# G851B.net
KiCad netlist of a schematic drawn in EAGLE
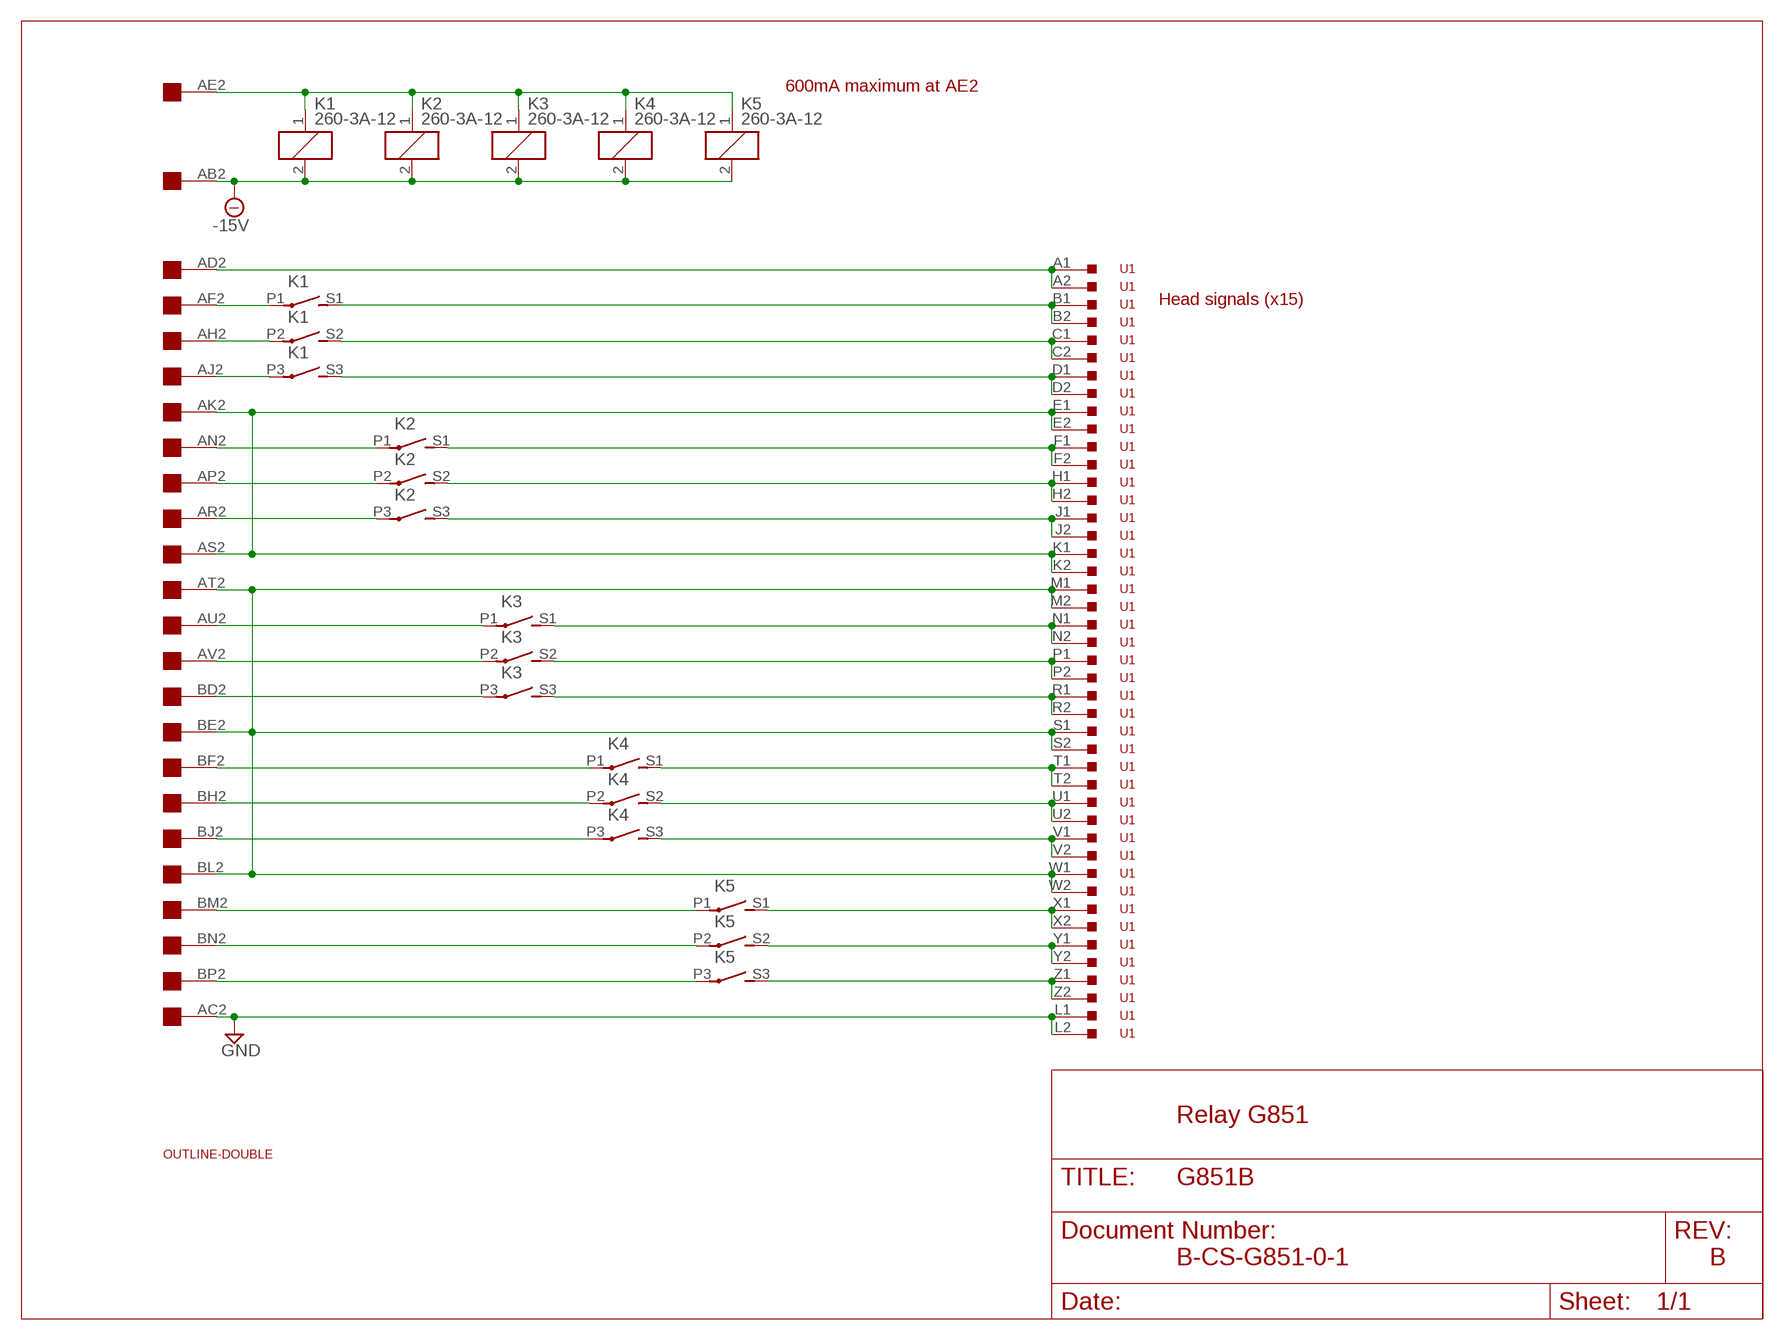
[diagram p0: schematic, sheet 1]

(export (version "E")
  (design (tool "Eeschema 10.0.6"))
  (components
    (comp (ref "K1")
      (value "260-3A-12")
      (footprint "eagle-import:260-3A-12")
      (libsource (lib "eagle-import") (part "260-3A-12"))
    )
    (comp (ref "K2")
      (value "260-3A-12")
      (footprint "eagle-import:260-3A-12")
      (libsource (lib "eagle-import") (part "260-3A-12"))
    )
    (comp (ref "K3")
      (value "260-3A-12")
      (footprint "eagle-import:260-3A-12")
      (libsource (lib "eagle-import") (part "260-3A-12"))
    )
    (comp (ref "K4")
      (value "260-3A-12")
      (footprint "eagle-import:260-3A-12")
      (libsource (lib "eagle-import") (part "260-3A-12"))
    )
    (comp (ref "K5")
      (value "260-3A-12")
      (footprint "eagle-import:260-3A-12")
      (libsource (lib "eagle-import") (part "260-3A-12"))
    )
    (comp (ref "U$1")
      (value "DOUBLE")
      (footprint "eagle-import:EDGE-CON4")
      (libsource (lib "eagle-import") (part "DOUBLE"))
    )
    (comp (ref "U$3")
      (value "OUTLINE-DOUBLE")
      (footprint "eagle-import:DOUBLE")
      (libsource (lib "eagle-import") (part "OUTLINE-DOUBLE"))
    )
    (comp (ref "U1")
      (value "133-022-03")
      (footprint "eagle-import:133-022-03")
      (libsource (lib "eagle-import") (part "133-022-03"))
    )
  )
  (nets
    (net (code "1") (name "-15V") (class "Default")
      (node (ref "K1") (pin "2") (pinfunction "2_2") (pintype "passive"))
      (node (ref "K2") (pin "2") (pinfunction "2_2") (pintype "passive"))
      (node (ref "K3") (pin "2") (pinfunction "2_2") (pintype "passive"))
      (node (ref "K4") (pin "2") (pinfunction "2_2") (pintype "passive"))
      (node (ref "K5") (pin "2") (pinfunction "2_2") (pintype "passive"))
      (node (ref "U$1") (pin "AB2") (pinfunction "1_AB2") (pintype "bidirectional"))
    )
    (net (code "2") (name "GND") (class "Default")
      (node (ref "U$1") (pin "AC2") (pinfunction "1_AC2") (pintype "bidirectional"))
      (node (ref "U1") (pin "L1") (pinfunction "P$2_L1") (pintype "bidirectional"))
      (node (ref "U1") (pin "L2") (pinfunction "P$2_L2") (pintype "bidirectional"))
    )
    (net (code "3") (name "Net-(K1B-P)") (class "Default")
      (node (ref "K1") (pin "P1") (pinfunction "P_P1") (pintype "passive"))
      (node (ref "U$1") (pin "AF2") (pinfunction "1_AF2") (pintype "bidirectional"))
    )
    (net (code "4") (name "Net-(K1B-S)") (class "Default")
      (node (ref "K1") (pin "S1") (pinfunction "S_S1") (pintype "passive"))
      (node (ref "U1") (pin "B1") (pinfunction "P$2_B1") (pintype "bidirectional"))
      (node (ref "U1") (pin "B2") (pinfunction "P$2_B2") (pintype "bidirectional"))
    )
    (net (code "5") (name "Net-(K1C-P)") (class "Default")
      (node (ref "K1") (pin "P2") (pinfunction "P_P2") (pintype "passive"))
      (node (ref "U$1") (pin "AH2") (pinfunction "1_AH2") (pintype "bidirectional"))
    )
    (net (code "6") (name "Net-(K1C-S)") (class "Default")
      (node (ref "K1") (pin "S2") (pinfunction "S_S2") (pintype "passive"))
      (node (ref "U1") (pin "C1") (pinfunction "P$2_C1") (pintype "bidirectional"))
      (node (ref "U1") (pin "C2") (pinfunction "P$2_C2") (pintype "bidirectional"))
    )
    (net (code "7") (name "Net-(K1D-P)") (class "Default")
      (node (ref "K1") (pin "P3") (pinfunction "P_P3") (pintype "passive"))
      (node (ref "U$1") (pin "AJ2") (pinfunction "1_AJ2") (pintype "bidirectional"))
    )
    (net (code "8") (name "Net-(K1D-S)") (class "Default")
      (node (ref "K1") (pin "S3") (pinfunction "S_S3") (pintype "passive"))
      (node (ref "U1") (pin "D1") (pinfunction "P$2_D1") (pintype "bidirectional"))
      (node (ref "U1") (pin "D2") (pinfunction "P$2_D2") (pintype "bidirectional"))
    )
    (net (code "9") (name "Net-(K2B-P)") (class "Default")
      (node (ref "K2") (pin "P1") (pinfunction "P_P1") (pintype "passive"))
      (node (ref "U$1") (pin "AN2") (pinfunction "1_AN2") (pintype "bidirectional"))
    )
    (net (code "10") (name "Net-(K2B-S)") (class "Default")
      (node (ref "K2") (pin "S1") (pinfunction "S_S1") (pintype "passive"))
      (node (ref "U1") (pin "F1") (pinfunction "P$2_F1") (pintype "bidirectional"))
      (node (ref "U1") (pin "F2") (pinfunction "P$2_F2") (pintype "bidirectional"))
    )
    (net (code "11") (name "Net-(K2C-P)") (class "Default")
      (node (ref "K2") (pin "P2") (pinfunction "P_P2") (pintype "passive"))
      (node (ref "U$1") (pin "AP2") (pinfunction "1_AP2") (pintype "bidirectional"))
    )
    (net (code "12") (name "Net-(K2C-S)") (class "Default")
      (node (ref "K2") (pin "S2") (pinfunction "S_S2") (pintype "passive"))
      (node (ref "U1") (pin "H1") (pinfunction "P$2_H1") (pintype "bidirectional"))
      (node (ref "U1") (pin "H2") (pinfunction "P$2_H2") (pintype "bidirectional"))
    )
    (net (code "13") (name "Net-(K2D-P)") (class "Default")
      (node (ref "K2") (pin "P3") (pinfunction "P_P3") (pintype "passive"))
      (node (ref "U$1") (pin "AR2") (pinfunction "1_AR2") (pintype "bidirectional"))
    )
    (net (code "14") (name "Net-(K2D-S)") (class "Default")
      (node (ref "K2") (pin "S3") (pinfunction "S_S3") (pintype "passive"))
      (node (ref "U1") (pin "J1") (pinfunction "P$2_J1") (pintype "bidirectional"))
      (node (ref "U1") (pin "J2") (pinfunction "P$2_J2") (pintype "bidirectional"))
    )
    (net (code "15") (name "Net-(K3B-P)") (class "Default")
      (node (ref "K3") (pin "P1") (pinfunction "P_P1") (pintype "passive"))
      (node (ref "U$1") (pin "AU2") (pinfunction "1_AU2") (pintype "bidirectional"))
    )
    (net (code "16") (name "Net-(K3B-S)") (class "Default")
      (node (ref "K3") (pin "S1") (pinfunction "S_S1") (pintype "passive"))
      (node (ref "U1") (pin "N1") (pinfunction "P$2_N1") (pintype "bidirectional"))
      (node (ref "U1") (pin "N2") (pinfunction "P$2_N2") (pintype "bidirectional"))
    )
    (net (code "17") (name "Net-(K3C-P)") (class "Default")
      (node (ref "K3") (pin "P2") (pinfunction "P_P2") (pintype "passive"))
      (node (ref "U$1") (pin "AV2") (pinfunction "1_AV2") (pintype "bidirectional"))
    )
    (net (code "18") (name "Net-(K3C-S)") (class "Default")
      (node (ref "K3") (pin "S2") (pinfunction "S_S2") (pintype "passive"))
      (node (ref "U1") (pin "P1") (pinfunction "P$2_P1") (pintype "bidirectional"))
      (node (ref "U1") (pin "P2") (pinfunction "P$2_P2") (pintype "bidirectional"))
    )
    (net (code "19") (name "Net-(K3D-P)") (class "Default")
      (node (ref "K3") (pin "P3") (pinfunction "P_P3") (pintype "passive"))
      (node (ref "U$1") (pin "BD2") (pinfunction "1_BD2") (pintype "bidirectional"))
    )
    (net (code "20") (name "Net-(K3D-S)") (class "Default")
      (node (ref "K3") (pin "S3") (pinfunction "S_S3") (pintype "passive"))
      (node (ref "U1") (pin "R1") (pinfunction "P$2_R1") (pintype "bidirectional"))
      (node (ref "U1") (pin "R2") (pinfunction "P$2_R2") (pintype "bidirectional"))
    )
    (net (code "21") (name "Net-(K4B-P)") (class "Default")
      (node (ref "K4") (pin "P1") (pinfunction "P_P1") (pintype "passive"))
      (node (ref "U$1") (pin "BF2") (pinfunction "1_BF2") (pintype "bidirectional"))
    )
    (net (code "22") (name "Net-(K4B-S)") (class "Default")
      (node (ref "K4") (pin "S1") (pinfunction "S_S1") (pintype "passive"))
      (node (ref "U1") (pin "T1") (pinfunction "P$2_T1") (pintype "bidirectional"))
      (node (ref "U1") (pin "T2") (pinfunction "P$2_T2") (pintype "bidirectional"))
    )
    (net (code "23") (name "Net-(K4C-P)") (class "Default")
      (node (ref "K4") (pin "P2") (pinfunction "P_P2") (pintype "passive"))
      (node (ref "U$1") (pin "BH2") (pinfunction "1_BH2") (pintype "bidirectional"))
    )
    (net (code "24") (name "Net-(K4C-S)") (class "Default")
      (node (ref "K4") (pin "S2") (pinfunction "S_S2") (pintype "passive"))
      (node (ref "U1") (pin "U1") (pinfunction "P$2_U1") (pintype "bidirectional"))
      (node (ref "U1") (pin "U2") (pinfunction "P$2_U2") (pintype "bidirectional"))
    )
    (net (code "25") (name "Net-(K4D-P)") (class "Default")
      (node (ref "K4") (pin "P3") (pinfunction "P_P3") (pintype "passive"))
      (node (ref "U$1") (pin "BJ2") (pinfunction "1_BJ2") (pintype "bidirectional"))
    )
    (net (code "26") (name "Net-(K4D-S)") (class "Default")
      (node (ref "K4") (pin "S3") (pinfunction "S_S3") (pintype "passive"))
      (node (ref "U1") (pin "V1") (pinfunction "P$2_V1") (pintype "bidirectional"))
      (node (ref "U1") (pin "V2") (pinfunction "P$2_V2") (pintype "bidirectional"))
    )
    (net (code "27") (name "Net-(K5B-P)") (class "Default")
      (node (ref "K5") (pin "P1") (pinfunction "P_P1") (pintype "passive"))
      (node (ref "U$1") (pin "BM2") (pinfunction "1_BM2") (pintype "bidirectional"))
    )
    (net (code "28") (name "Net-(K5B-S)") (class "Default")
      (node (ref "K5") (pin "S1") (pinfunction "S_S1") (pintype "passive"))
      (node (ref "U1") (pin "X1") (pinfunction "P$2_X1") (pintype "bidirectional"))
      (node (ref "U1") (pin "X2") (pinfunction "P$2_X2") (pintype "bidirectional"))
    )
    (net (code "29") (name "Net-(K5C-P)") (class "Default")
      (node (ref "K5") (pin "P2") (pinfunction "P_P2") (pintype "passive"))
      (node (ref "U$1") (pin "BN2") (pinfunction "1_BN2") (pintype "bidirectional"))
    )
    (net (code "30") (name "Net-(K5C-S)") (class "Default")
      (node (ref "K5") (pin "S2") (pinfunction "S_S2") (pintype "passive"))
      (node (ref "U1") (pin "Y1") (pinfunction "P$2_Y1") (pintype "bidirectional"))
      (node (ref "U1") (pin "Y2") (pinfunction "P$2_Y2") (pintype "bidirectional"))
    )
    (net (code "31") (name "Net-(K5D-P)") (class "Default")
      (node (ref "K5") (pin "P3") (pinfunction "P_P3") (pintype "passive"))
      (node (ref "U$1") (pin "BP2") (pinfunction "1_BP2") (pintype "bidirectional"))
    )
    (net (code "32") (name "Net-(K5D-S)") (class "Default")
      (node (ref "K5") (pin "S3") (pinfunction "S_S3") (pintype "passive"))
      (node (ref "U1") (pin "Z1") (pinfunction "P$2_Z1") (pintype "bidirectional"))
      (node (ref "U1") (pin "Z2") (pinfunction "P$2_Z2") (pintype "bidirectional"))
    )
    (net (code "33") (name "Net-(U$1AD-1)") (class "Default")
      (node (ref "U$1") (pin "AK2") (pinfunction "1_AK2") (pintype "bidirectional"))
      (node (ref "U$1") (pin "AS2") (pinfunction "1_AS2") (pintype "bidirectional"))
      (node (ref "U1") (pin "E1") (pinfunction "P$2_E1") (pintype "bidirectional"))
      (node (ref "U1") (pin "E2") (pinfunction "P$2_E2") (pintype "bidirectional"))
      (node (ref "U1") (pin "K1") (pinfunction "P$2_K1") (pintype "bidirectional"))
      (node (ref "U1") (pin "K2") (pinfunction "P$2_K2") (pintype "bidirectional"))
    )
    (net (code "34") (name "Net-(U$1AF-1)") (class "Default")
      (node (ref "U$1") (pin "AT2") (pinfunction "1_AT2") (pintype "bidirectional"))
      (node (ref "U$1") (pin "BE2") (pinfunction "1_BE2") (pintype "bidirectional"))
      (node (ref "U$1") (pin "BL2") (pinfunction "1_BL2") (pintype "bidirectional"))
      (node (ref "U1") (pin "M1") (pinfunction "P$2_M1") (pintype "bidirectional"))
      (node (ref "U1") (pin "M2") (pinfunction "P$2_M2") (pintype "bidirectional"))
      (node (ref "U1") (pin "S1") (pinfunction "P$2_S1") (pintype "bidirectional"))
      (node (ref "U1") (pin "S2") (pinfunction "P$2_S2") (pintype "bidirectional"))
      (node (ref "U1") (pin "W1") (pinfunction "P$2_W1") (pintype "bidirectional"))
      (node (ref "U1") (pin "W2") (pinfunction "P$2_W2") (pintype "bidirectional"))
    )
    (net (code "35") (name "Net-(U$1H-1)") (class "Default")
      (node (ref "U$1") (pin "AD2") (pinfunction "1_AD2") (pintype "bidirectional"))
      (node (ref "U1") (pin "A1") (pinfunction "P$2_A1") (pintype "bidirectional"))
      (node (ref "U1") (pin "A2") (pinfunction "P$2_A2") (pintype "bidirectional"))
    )
    (net (code "36") (name "Net-(U$1J-1)") (class "Default")
      (node (ref "K1") (pin "1") (pinfunction "1_1") (pintype "passive"))
      (node (ref "K2") (pin "1") (pinfunction "1_1") (pintype "passive"))
      (node (ref "K3") (pin "1") (pinfunction "1_1") (pintype "passive"))
      (node (ref "K4") (pin "1") (pinfunction "1_1") (pintype "passive"))
      (node (ref "K5") (pin "1") (pinfunction "1_1") (pintype "passive"))
      (node (ref "U$1") (pin "AE2") (pinfunction "1_AE2") (pintype "bidirectional"))
    )
  )
)
